# flash.net
KiCad netlist of a schematic drawn in Altium Designer
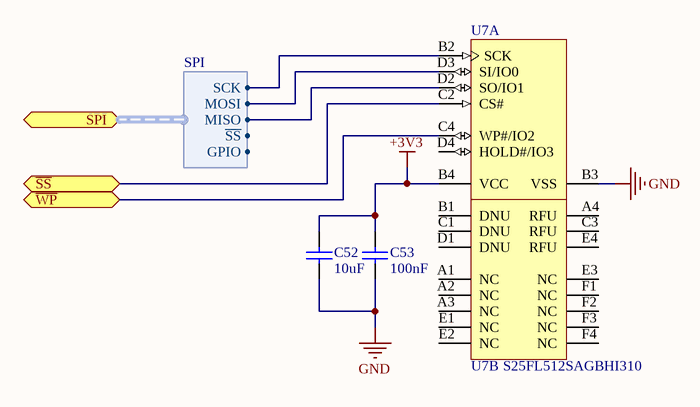
[diagram p0: flash.SchDoc]

(export (version "E")
  (design (tool "Eeschema 10.0.6"))
  (components
    (comp (ref "C52")
      (value "10uF")
      (footprint "C2012")
      (description "Capacitor")
      (fields
        (field (name "MANUFACTURER") "MULTICOMP")
        (field (name "MANUFACTURER PART NUMBER") "MC0805X106K250CT")
        (field (name "PUBLISHER") "Altium Limited")
      )
      (libsource (lib "Miscellaneous Devices") (part "Cap"))
    )
    (comp (ref "C53")
      (value "100nF")
      (footprint "C2012")
      (description "Capacitor")
      (fields
        (field (name "MANUFACTURER") "MULTICOMP")
        (field (name "MANUFACTURER PART NUMBER") "MC0805B104K500CT")
        (field (name "PUBLISHER") "Altium Limited")
      )
      (libsource (lib "Miscellaneous Devices") (part "Cap"))
    )
    (comp (ref "U7")
      (value "S25FL512SAGBHI310")
      (footprint "SPSN-FAC024")
      (fields (field (name "PARTNUMBER") "S25FL128SAGBHI310") (field (name "MANUFACTURER") "Spansion"))
      (libsource (lib "Altium Content Vault") (part "CMP-1329-00014-1"))
    )
  )
  (nets
    (net (code "2") (name "+3V3") (class "Default")
      (node (ref "C52") (pin "1") (pinfunction "1_1") (pintype "passive"))
      (node (ref "C53") (pin "1") (pinfunction "1_1") (pintype "passive"))
      (node (ref "U7") (pin "B4") (pinfunction "VCC_B4") (pintype "power_in"))
    )
    (net (code "3") (name "/MISO") (class "Default")
      (node (ref "U7") (pin "D2") (pinfunction "SO/IO1_D2") (pintype "bidirectional"))
    )
    (net (code "4") (name "/MOSI") (class "Default")
      (node (ref "U7") (pin "D3") (pinfunction "SI/IO0_D3") (pintype "bidirectional"))
    )
    (net (code "5") (name "/SCK") (class "Default")
      (node (ref "U7") (pin "B2") (pinfunction "SCK_B2") (pintype "input"))
    )
    (net (code "6") (name "/SS") (class "Default")
      (node (ref "U7") (pin "C2") (pinfunction "CS#_C2") (pintype "input"))
    )
    (net (code "7") (name "/WP") (class "Default")
      (node (ref "U7") (pin "C4") (pinfunction "WP#/IO2_C4") (pintype "bidirectional"))
    )
    (net (code "9") (name "GND") (class "Default")
      (node (ref "C52") (pin "2") (pinfunction "2_2") (pintype "passive"))
      (node (ref "C53") (pin "2") (pinfunction "2_2") (pintype "passive"))
      (node (ref "U7") (pin "B3") (pinfunction "VSS_B3") (pintype "power_in"))
    )
    (net (code "10") (name "unconnected-(U7A-HOLD#{slash}IO3-PadD4)") (class "Default")
      (node (ref "U7") (pin "D4") (pinfunction "HOLD#/IO3_D4") (pintype "bidirectional"))
    )
    (net (code "11") (name "unconnected-(U7B-DNU-PadB1)") (class "Default")
      (node (ref "U7") (pin "B1") (pinfunction "DNU_B1") (pintype "passive"))
    )
    (net (code "12") (name "unconnected-(U7B-DNU-PadC1)") (class "Default")
      (node (ref "U7") (pin "C1") (pinfunction "DNU_C1") (pintype "passive"))
    )
    (net (code "13") (name "unconnected-(U7B-DNU-PadD1)") (class "Default")
      (node (ref "U7") (pin "D1") (pinfunction "DNU_D1") (pintype "passive"))
    )
    (net (code "14") (name "unconnected-(U7B-NC-PadA1)") (class "Default")
      (node (ref "U7") (pin "A1") (pinfunction "NC_A1") (pintype "passive"))
    )
    (net (code "15") (name "unconnected-(U7B-NC-PadA2)") (class "Default")
      (node (ref "U7") (pin "A2") (pinfunction "NC_A2") (pintype "passive"))
    )
    (net (code "16") (name "unconnected-(U7B-NC-PadA3)") (class "Default")
      (node (ref "U7") (pin "A3") (pinfunction "NC_A3") (pintype "passive"))
    )
    (net (code "17") (name "unconnected-(U7B-NC-PadE1)") (class "Default")
      (node (ref "U7") (pin "E1") (pinfunction "NC_E1") (pintype "passive"))
    )
    (net (code "18") (name "unconnected-(U7B-NC-PadE2)") (class "Default")
      (node (ref "U7") (pin "E2") (pinfunction "NC_E2") (pintype "passive"))
    )
    (net (code "19") (name "unconnected-(U7B-NC-PadE3)") (class "Default")
      (node (ref "U7") (pin "E3") (pinfunction "NC_E3") (pintype "passive"))
    )
    (net (code "20") (name "unconnected-(U7B-NC-PadF1)") (class "Default")
      (node (ref "U7") (pin "F1") (pinfunction "NC_F1") (pintype "passive"))
    )
    (net (code "21") (name "unconnected-(U7B-NC-PadF2)") (class "Default")
      (node (ref "U7") (pin "F2") (pinfunction "NC_F2") (pintype "passive"))
    )
    (net (code "22") (name "unconnected-(U7B-NC-PadF3)") (class "Default")
      (node (ref "U7") (pin "F3") (pinfunction "NC_F3") (pintype "passive"))
    )
    (net (code "23") (name "unconnected-(U7B-NC-PadF4)") (class "Default")
      (node (ref "U7") (pin "F4") (pinfunction "NC_F4") (pintype "passive"))
    )
    (net (code "24") (name "unconnected-(U7B-RFU-PadA4)") (class "Default")
      (node (ref "U7") (pin "A4") (pinfunction "RFU_A4") (pintype "passive"))
    )
    (net (code "25") (name "unconnected-(U7B-RFU-PadC3)") (class "Default")
      (node (ref "U7") (pin "C3") (pinfunction "RFU_C3") (pintype "passive"))
    )
    (net (code "26") (name "unconnected-(U7B-RFU-PadE4)") (class "Default")
      (node (ref "U7") (pin "E4") (pinfunction "RFU_E4") (pintype "passive"))
    )
  )
)
